# fullCURRENT_smarts_micro.net
KiCad netlist of a schematic drawn in Altium Designer
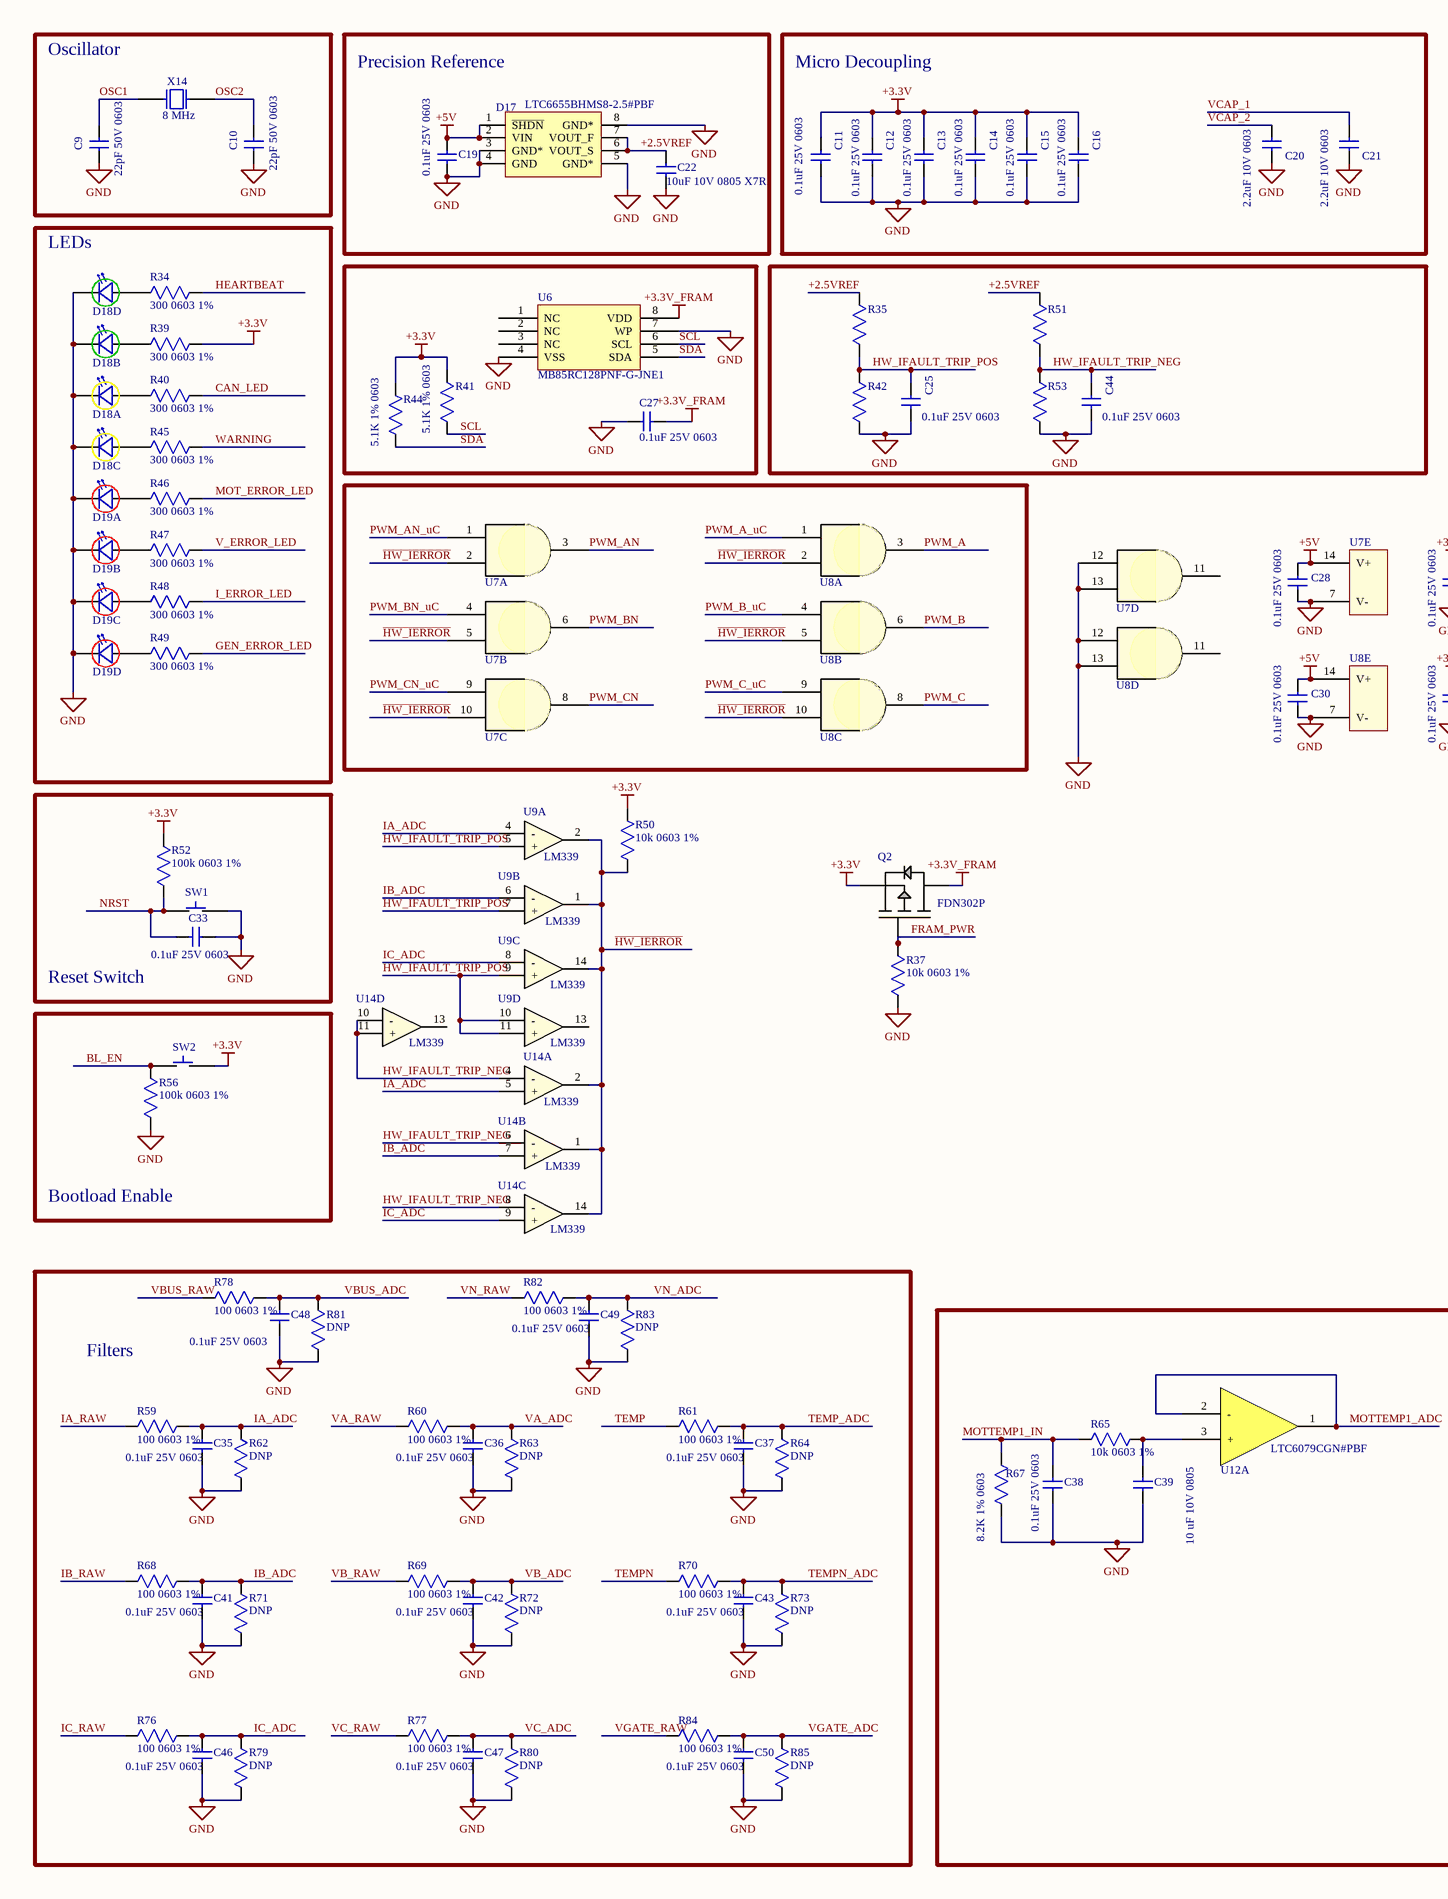
[diagram p0: fullCURRENT smarts micro.SchDoc, left]
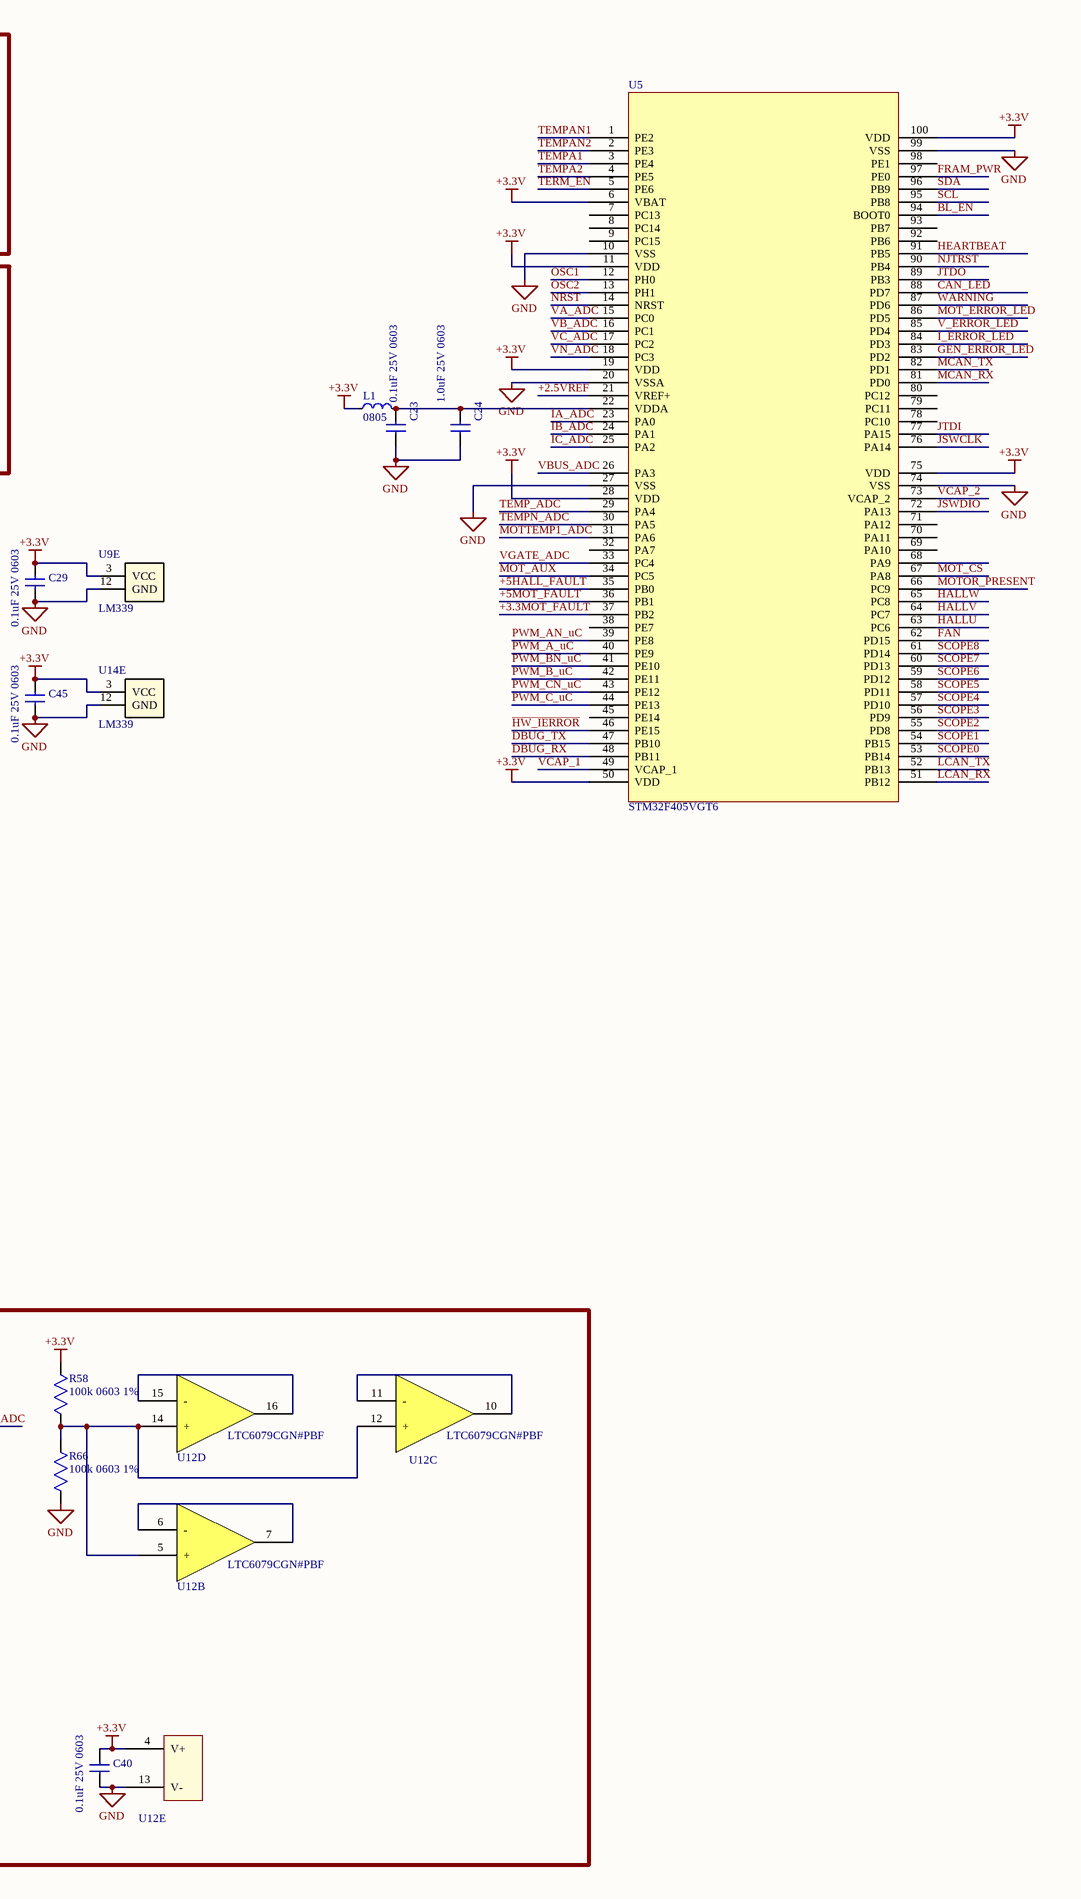
[diagram p1: fullCURRENT smarts micro.SchDoc, right]

(export (version "E")
  (design (tool "Eeschema 10.0.6"))
  (components
    (comp (ref "C9")
      (value "22pF 50V 0603")
      (footprint "0603_cap")
      (description "CAP CER 22PF 50V 5% NPO 0603")
      (fields (field (name "Comment") "CAP 0603"))
      (libsource (lib "Nutz") (part "C_0603"))
    )
    (comp (ref "C10")
      (value "22pF 50V 0603")
      (footprint "0603_cap")
      (description "CAP CER 22PF 50V 5% NPO 0603")
      (fields (field (name "Comment") "CAP 0603"))
      (libsource (lib "Nutz") (part "C_0603"))
    )
    (comp (ref "C11")
      (value "0.1uF 25V 0603")
      (footprint "0603_cap")
      (description "CAP CER 0.1UF 25V X7R 0603")
      (fields (field (name "PART NUMBER") "GRM188R71E104KA01D") (field (name "Comment") "CAP 0603"))
      (libsource (lib "Nutz") (part "C_0603"))
    )
    (comp (ref "C12")
      (value "0.1uF 25V 0603")
      (footprint "0603_cap")
      (description "CAP CER 0.1UF 25V X7R 0603")
      (fields (field (name "PART NUMBER") "GRM188R71E104KA01D") (field (name "Comment") "CAP 0603"))
      (libsource (lib "Nutz") (part "C_0603"))
    )
    (comp (ref "C13")
      (value "0.1uF 25V 0603")
      (footprint "0603_cap")
      (description "CAP CER 0.1UF 25V X7R 0603")
      (fields (field (name "PART NUMBER") "GRM188R71E104KA01D") (field (name "Comment") "CAP 0603"))
      (libsource (lib "Nutz") (part "C_0603"))
    )
    (comp (ref "C14")
      (value "0.1uF 25V 0603")
      (footprint "0603_cap")
      (description "CAP CER 0.1UF 25V X7R 0603")
      (fields (field (name "PART NUMBER") "GRM188R71E104KA01D") (field (name "Comment") "CAP 0603"))
      (libsource (lib "Nutz") (part "C_0603"))
    )
    (comp (ref "C15")
      (value "0.1uF 25V 0603")
      (footprint "0603_cap")
      (description "CAP CER 0.1UF 25V X7R 0603")
      (fields (field (name "PART NUMBER") "GRM188R71E104KA01D") (field (name "Comment") "CAP 0603"))
      (libsource (lib "Nutz") (part "C_0603"))
    )
    (comp (ref "C16")
      (value "0.1uF 25V 0603")
      (footprint "0603_cap")
      (description "CAP CER 0.1UF 25V X7R 0603")
      (fields (field (name "PART NUMBER") "GRM188R71E104KA01D") (field (name "Comment") "CAP 0603"))
      (libsource (lib "Nutz") (part "C_0603"))
    )
    (comp (ref "C19")
      (value "0.1uF 25V 0603")
      (footprint "0603_cap")
      (description "CAP CER 0.1UF 25V X7R 0603")
      (fields (field (name "Comment") "CAP 0603"))
      (libsource (lib "Nutz") (part "C_0603"))
    )
    (comp (ref "C20")
      (value "2.2uF 10V 0603")
      (footprint "0603_cap")
      (description "CAP CER 2.2UF 10V 10% X7R 0603")
      (fields (field (name "MANUFACTURER") "Taiyo Yuden") (field (name "PART NUMBER") "LMK107B7225KA-T"))
      (libsource (lib "Nutz") (part "C_0603"))
    )
    (comp (ref "C21")
      (value "2.2uF 10V 0603")
      (footprint "0603_cap")
      (description "CAP CER 2.2UF 10V 10% X7R 0603")
      (fields (field (name "MANUFACTURER") "Taiyo Yuden") (field (name "PART NUMBER") "LMK107B7225KA-T"))
      (libsource (lib "Nutz") (part "C_0603"))
    )
    (comp (ref "C22")
      (value "10uF 10V 0805 X7R")
      (footprint "0805_Capacitor")
      (description "CAP CERM 0805")
      (fields (field (name "Comment") "CAP 0805"))
      (libsource (lib "Nutz") (part "C_0805"))
    )
    (comp (ref "C23")
      (value "0.1uF 25V 0603")
      (footprint "0603_cap")
      (description "CAP CER 0.1UF 25V X7R 0603")
      (fields (field (name "PART NUMBER") "GRM188R71E104KA01D") (field (name "Comment") "CAP 0603"))
      (libsource (lib "Nutz") (part "C_0603"))
    )
    (comp (ref "C24")
      (value "1.0uF 25V 0603")
      (footprint "0603_cap")
      (description "CAP CER 1.0UF 25V 10% X7R 0603")
      (fields (field (name "Comment") "CAP 0603"))
      (libsource (lib "Nutz") (part "C_0603"))
    )
    (comp (ref "C25")
      (value "0.1uF 25V 0603")
      (footprint "0603_cap")
      (description "CAP CER 0.1UF 25V X7R 0603")
      (fields (field (name "PART NUMBER") "GRM188R71E104KA01D") (field (name "Comment") "CAP 0603"))
      (libsource (lib "Nutz") (part "C_0603"))
    )
    (comp (ref "C27")
      (value "0.1uF 25V 0603")
      (footprint "0603_cap")
      (description "CAP CER 0.1UF 25V X7R 0603")
      (fields (field (name "Comment") "CAP 0603"))
      (libsource (lib "Nutz") (part "C_0603"))
    )
    (comp (ref "C28")
      (value "0.1uF 25V 0603")
      (footprint "0603_cap")
      (description "CAP CER 0.1UF 25V X7R 0603")
      (fields (field (name "PART NUMBER") "GRM188R71E104KA01D") (field (name "Comment") "CAP 0603"))
      (libsource (lib "Nutz") (part "C_0603"))
    )
    (comp (ref "C29")
      (value "0.1uF 25V 0603")
      (footprint "0603_cap")
      (description "CAP CER 0.1UF 25V X7R 0603")
      (fields (field (name "PART NUMBER") "GRM188R71E104KA01D") (field (name "Comment") "CAP 0603"))
      (libsource (lib "Nutz") (part "C_0603"))
    )
    (comp (ref "C30")
      (value "0.1uF 25V 0603")
      (footprint "0603_cap")
      (description "CAP CER 0.1UF 25V X7R 0603")
      (fields (field (name "PART NUMBER") "GRM188R71E104KA01D") (field (name "Comment") "CAP 0603"))
      (libsource (lib "Nutz") (part "C_0603"))
    )
    (comp (ref "C33")
      (value "0.1uF 25V 0603")
      (footprint "0603_cap")
      (description "CAP CER 0.1UF 25V X7R 0603")
      (fields (field (name "PART NUMBER") "GRM188R71E104KA01D") (field (name "Comment") "CAP 0603"))
      (libsource (lib "Nutz") (part "C_0603"))
    )
    (comp (ref "C35")
      (value "0.1uF 25V 0603")
      (footprint "0603_cap")
      (description "CAP CER 0.1UF 25V X7R 0603")
      (fields (field (name "Comment") "CAP 0603"))
      (libsource (lib "Nutz") (part "C_0603"))
    )
    (comp (ref "C36")
      (value "0.1uF 25V 0603")
      (footprint "0603_cap")
      (description "CAP CER 0.1UF 25V X7R 0603")
      (fields (field (name "Comment") "CAP 0603"))
      (libsource (lib "Nutz") (part "C_0603"))
    )
    (comp (ref "C37")
      (value "0.1uF 25V 0603")
      (footprint "0603_cap")
      (description "CAP CER 0.1UF 25V X7R 0603")
      (fields (field (name "Comment") "CAP 0603"))
      (libsource (lib "Nutz") (part "C_0603"))
    )
    (comp (ref "C38")
      (value "0.1uF 25V 0603")
      (footprint "0603_cap")
      (description "CAP CER 0.1UF 25V X7R 0603")
      (fields (field (name "Comment") "CAP 0603"))
      (libsource (lib "Nutz") (part "C_0603"))
    )
    (comp (ref "C39")
      (value "10 uF 10V 0805")
      (footprint "0805_Capacitor")
      (description "CAP CER 10UF 10V 10% X5R 0805")
      (fields (field (name "MANUFACTURER") "Taiyo Yuden") (field (name "Comment") "CAP 0805"))
      (libsource (lib "Nutz") (part "C_0805"))
    )
    (comp (ref "C40")
      (value "0.1uF 25V 0603")
      (footprint "0603_cap")
      (description "CAP CER 0.1UF 25V X7R 0603")
      (fields (field (name "PART NUMBER") "GRM188R71E104KA01D") (field (name "Comment") "CAP 0603"))
      (libsource (lib "Nutz") (part "C_0603"))
    )
    (comp (ref "C41")
      (value "0.1uF 25V 0603")
      (footprint "0603_cap")
      (description "CAP CER 0.1UF 25V X7R 0603")
      (fields (field (name "Comment") "CAP 0603"))
      (libsource (lib "Nutz") (part "C_0603"))
    )
    (comp (ref "C42")
      (value "0.1uF 25V 0603")
      (footprint "0603_cap")
      (description "CAP CER 0.1UF 25V X7R 0603")
      (fields (field (name "Comment") "CAP 0603"))
      (libsource (lib "Nutz") (part "C_0603"))
    )
    (comp (ref "C43")
      (value "0.1uF 25V 0603")
      (footprint "0603_cap")
      (description "CAP CER 0.1UF 25V X7R 0603")
      (fields (field (name "Comment") "CAP 0603"))
      (libsource (lib "Nutz") (part "C_0603"))
    )
    (comp (ref "C44")
      (value "0.1uF 25V 0603")
      (footprint "0603_cap")
      (description "CAP CER 0.1UF 25V X7R 0603")
      (fields (field (name "PART NUMBER") "GRM188R71E104KA01D") (field (name "Comment") "CAP 0603"))
      (libsource (lib "Nutz") (part "C_0603"))
    )
    (comp (ref "C45")
      (value "0.1uF 25V 0603")
      (footprint "0603_cap")
      (description "CAP CER 0.1UF 25V X7R 0603")
      (fields (field (name "PART NUMBER") "GRM188R71E104KA01D") (field (name "Comment") "CAP 0603"))
      (libsource (lib "Nutz") (part "C_0603"))
    )
    (comp (ref "C46")
      (value "0.1uF 25V 0603")
      (footprint "0603_cap")
      (description "CAP CER 0.1UF 25V X7R 0603")
      (fields (field (name "Comment") "CAP 0603"))
      (libsource (lib "Nutz") (part "C_0603"))
    )
    (comp (ref "C47")
      (value "0.1uF 25V 0603")
      (footprint "0603_cap")
      (description "CAP CER 0.1UF 25V X7R 0603")
      (fields (field (name "Comment") "CAP 0603"))
      (libsource (lib "Nutz") (part "C_0603"))
    )
    (comp (ref "C48")
      (value "0.1uF 25V 0603")
      (footprint "0603_cap")
      (description "CAP CER 0.1UF 25V X7R 0603")
      (fields (field (name "Comment") "CAP 0603"))
      (libsource (lib "Nutz") (part "C_0603"))
    )
    (comp (ref "C49")
      (value "0.1uF 25V 0603")
      (footprint "0603_cap")
      (description "CAP CER 0.1UF 25V X7R 0603")
      (fields (field (name "Comment") "CAP 0603"))
      (libsource (lib "Nutz") (part "C_0603"))
    )
    (comp (ref "C50")
      (value "0.1uF 25V 0603")
      (footprint "0603_cap")
      (description "CAP CER 0.1UF 25V X7R 0603")
      (fields (field (name "Comment") "CAP 0603"))
      (libsource (lib "Nutz") (part "C_0603"))
    )
    (comp (ref "D17")
      (value "D_LTC6655BHMS8-2.5#PBF")
      (footprint "TSOP65P490X110-8N")
      (description "IC VREF SERIES PREC 2.5V 8-MSOP")
      (fields
        (field (name "MANUFACTURER") "Linear Technology")
        (field (name "PART NUMBER") "LTC6655BHMS8-2.5#PBF")
      )
      (libsource (lib "c3_SchLib") (part "D_LTC6655BHMS8-3.3#PBF"))
    )
    (comp (ref "D18")
      (value "D_LED_4HIGH_2GREEN_2YELLOW")
      (footprint "DIALIGHT 568")
      (description "LED 4HI 3MM GRN/YEL/GRN/YEL PCMT")
      (fields (field (name "PART NUMBER") "568-0102-323F") (field (name "MANUFACTURER") "Dialight"))
      (libsource (lib "Nutz") (part "D_LED_4HIGH_2GREEN_2YELLOW"))
    )
    (comp (ref "D19")
      (value "D_LED_4HIGH_RED")
      (footprint "DIALIGHT 568")
      (description "LED 4HI 3MM 5V RED PC MNT")
      (fields (field (name "PART NUMBER") "568-0301-111F") (field (name "MANUFACTURER") "Dialight"))
      (libsource (lib "Nutz") (part "D_LED_4HIGH_RED"))
    )
    (comp (ref "L1")
      (value "0805")
      (footprint "0805_Resistor")
      (description "FERRITE 0603")
      (libsource (lib "d1_SchLib") (part "L_1mH_10%"))
    )
    (comp (ref "Q2")
      (value "FDN302P")
      (footprint "SOT-23")
      (description "MOSFET P-CH 20V 2.4A SSOT3")
      (fields
        (field (name "MANUFACTURER") "Fairchild Semiconductor")
        (field (name "SVP CREATOR") "Adam Shea")
        (field (name "SVP REVIEWER 1") "Nate Bolyard")
        (field (name "SVP REVIEWER 2") "Trevtron")
      )
      (libsource (lib "d1_SchLib") (part "Q_FDN302P"))
    )
    (comp (ref "R34")
      (value "300 0603 1%")
      (footprint "0603_res")
      (description "RES 300 0603 1%")
      (fields (field (name "Comment") "RES 0603"))
      (libsource (lib "Nutz") (part "R_0603"))
    )
    (comp (ref "R35")
      (value "RES 0603")
      (footprint "0603_res")
      (description "RES DNP 0603 0.1%")
      (libsource (lib "Nutz") (part "R_0603"))
    )
    (comp (ref "R37")
      (value "10k 0603 1%")
      (footprint "0603_res")
      (description "RES 10K 0603 1%")
      (fields (field (name "Comment") "RES 0603"))
      (libsource (lib "Nutz") (part "R_0603"))
    )
    (comp (ref "R39")
      (value "300 0603 1%")
      (footprint "0603_res")
      (description "RES 300 0603 1%")
      (fields (field (name "Comment") "RES 0603"))
      (libsource (lib "Nutz") (part "R_0603"))
    )
    (comp (ref "R40")
      (value "300 0603 1%")
      (footprint "0603_res")
      (description "RES 300 0603 1%")
      (fields (field (name "Comment") "RES 0603"))
      (libsource (lib "Nutz") (part "R_0603"))
    )
    (comp (ref "R41")
      (value "5.1K 1% 0603")
      (footprint "0603_res")
      (description "RES 5.1K 1% 0603")
      (fields (field (name "Comment") "RES 0603"))
      (libsource (lib "Nutz") (part "R_0603"))
    )
    (comp (ref "R42")
      (value "RES 0603")
      (footprint "0603_res")
      (description "RES DNP 0603 0.1%")
      (libsource (lib "Nutz") (part "R_0603"))
    )
    (comp (ref "R44")
      (value "5.1K 1% 0603")
      (footprint "0603_res")
      (description "RES 5.1K 1% 0603")
      (fields (field (name "Comment") "RES 0603"))
      (libsource (lib "Nutz") (part "R_0603"))
    )
    (comp (ref "R45")
      (value "300 0603 1%")
      (footprint "0603_res")
      (description "RES 300 0603 1%")
      (fields (field (name "Comment") "RES 0603"))
      (libsource (lib "Nutz") (part "R_0603"))
    )
    (comp (ref "R46")
      (value "300 0603 1%")
      (footprint "0603_res")
      (description "RES 300 0603 1%")
      (fields (field (name "Comment") "RES 0603"))
      (libsource (lib "Nutz") (part "R_0603"))
    )
    (comp (ref "R47")
      (value "300 0603 1%")
      (footprint "0603_res")
      (description "RES 300 0603 1%")
      (fields (field (name "Comment") "RES 0603"))
      (libsource (lib "Nutz") (part "R_0603"))
    )
    (comp (ref "R48")
      (value "300 0603 1%")
      (footprint "0603_res")
      (description "RES 300 0603 1%")
      (fields (field (name "Comment") "RES 0603"))
      (libsource (lib "Nutz") (part "R_0603"))
    )
    (comp (ref "R49")
      (value "300 0603 1%")
      (footprint "0603_res")
      (description "RES 300 0603 1%")
      (fields (field (name "Comment") "RES 0603"))
      (libsource (lib "Nutz") (part "R_0603"))
    )
    (comp (ref "R50")
      (value "10k 0603 1%")
      (footprint "0603_res")
      (description "RES 10K 0603 1%")
      (fields (field (name "Comment") "RES 0603"))
      (libsource (lib "Nutz") (part "R_0603"))
    )
    (comp (ref "R51")
      (value "RES 0603")
      (footprint "0603_res")
      (description "RES DNP 0603 0.1%")
      (libsource (lib "Nutz") (part "R_0603"))
    )
    (comp (ref "R52")
      (value "100k 0603 1%")
      (footprint "0603_res")
      (description "RES 100K 0603 1%")
      (fields (field (name "Comment") "RES 0603"))
      (libsource (lib "Nutz") (part "R_0603"))
    )
    (comp (ref "R53")
      (value "RES 0603")
      (footprint "0603_res")
      (description "RES DNP 0603 0.1%")
      (libsource (lib "Nutz") (part "R_0603"))
    )
    (comp (ref "R56")
      (value "100k 0603 1%")
      (footprint "0603_res")
      (description "RES 100K 0603 1%")
      (fields (field (name "Comment") "RES 0603"))
      (libsource (lib "Nutz") (part "R_0603"))
    )
    (comp (ref "R58")
      (value "100k 0603 1%")
      (footprint "0603_res")
      (description "RES 100K 0603 1%")
      (fields (field (name "Comment") "RES 0603"))
      (libsource (lib "Nutz") (part "R_0603"))
    )
    (comp (ref "R59")
      (value "100 0603 1%")
      (footprint "0603_res")
      (description "RES 100 0603 1%")
      (fields (field (name "Comment") "RES 0603"))
      (libsource (lib "Nutz") (part "R_0603"))
    )
    (comp (ref "R60")
      (value "100 0603 1%")
      (footprint "0603_res")
      (description "RES 100 0603 1%")
      (fields (field (name "Comment") "RES 0603"))
      (libsource (lib "Nutz") (part "R_0603"))
    )
    (comp (ref "R61")
      (value "100 0603 1%")
      (footprint "0603_res")
      (description "RES 100 0603 1%")
      (fields (field (name "Comment") "RES 0603"))
      (libsource (lib "Nutz") (part "R_0603"))
    )
    (comp (ref "R62")
      (value "DNP")
      (footprint "0603_res")
      (description "RES 0603 DNP")
      (fields (field (name "Comment") "RES 0603"))
      (libsource (lib "Nutz") (part "R_0603"))
    )
    (comp (ref "R63")
      (value "DNP")
      (footprint "0603_res")
      (description "RES 0603 DNP")
      (fields (field (name "Comment") "RES 0603"))
      (libsource (lib "Nutz") (part "R_0603"))
    )
    (comp (ref "R64")
      (value "DNP")
      (footprint "0603_res")
      (description "RES 0603 DNP")
      (fields (field (name "Comment") "RES 0603"))
      (libsource (lib "Nutz") (part "R_0603"))
    )
    (comp (ref "R65")
      (value "10k 0603 1%")
      (footprint "0603_res")
      (description "RES 10K 0603 1%")
      (fields (field (name "Comment") "RES 0603"))
      (libsource (lib "Nutz") (part "R_0603"))
    )
    (comp (ref "R66")
      (value "100k 0603 1%")
      (footprint "0603_res")
      (description "RES 100K 0603 1%")
      (fields (field (name "Comment") "RES 0603"))
      (libsource (lib "Nutz") (part "R_0603"))
    )
    (comp (ref "R67")
      (value "8.2K 1% 0603")
      (footprint "0603_res")
      (description "RES 8.2K 1% 0603")
      (fields (field (name "Comment") "RES 0603"))
      (libsource (lib "Nutz") (part "R_0603"))
    )
    (comp (ref "R68")
      (value "100 0603 1%")
      (footprint "0603_res")
      (description "RES 100 0603 1%")
      (fields (field (name "Comment") "RES 0603"))
      (libsource (lib "Nutz") (part "R_0603"))
    )
    (comp (ref "R69")
      (value "100 0603 1%")
      (footprint "0603_res")
      (description "RES 100 0603 1%")
      (fields (field (name "Comment") "RES 0603"))
      (libsource (lib "Nutz") (part "R_0603"))
    )
    (comp (ref "R70")
      (value "100 0603 1%")
      (footprint "0603_res")
      (description "RES 100 0603 1%")
      (fields (field (name "Comment") "RES 0603"))
      (libsource (lib "Nutz") (part "R_0603"))
    )
    (comp (ref "R71")
      (value "DNP")
      (footprint "0603_res")
      (description "RES 0603 DNP")
      (fields (field (name "Comment") "RES 0603"))
      (libsource (lib "Nutz") (part "R_0603"))
    )
    (comp (ref "R72")
      (value "DNP")
      (footprint "0603_res")
      (description "RES 0603 DNP")
      (fields (field (name "Comment") "RES 0603"))
      (libsource (lib "Nutz") (part "R_0603"))
    )
    (comp (ref "R73")
      (value "DNP")
      (footprint "0603_res")
      (description "RES 0603 DNP")
      (fields (field (name "Comment") "RES 0603"))
      (libsource (lib "Nutz") (part "R_0603"))
    )
    (comp (ref "R76")
      (value "100 0603 1%")
      (footprint "0603_res")
      (description "RES 100 0603 1%")
      (fields (field (name "Comment") "RES 0603"))
      (libsource (lib "Nutz") (part "R_0603"))
    )
    (comp (ref "R77")
      (value "100 0603 1%")
      (footprint "0603_res")
      (description "RES 100 0603 1%")
      (fields (field (name "Comment") "RES 0603"))
      (libsource (lib "Nutz") (part "R_0603"))
    )
    (comp (ref "R78")
      (value "100 0603 1%")
      (footprint "0603_res")
      (description "RES 100 0603 1%")
      (fields (field (name "Comment") "RES 0603"))
      (libsource (lib "Nutz") (part "R_0603"))
    )
    (comp (ref "R79")
      (value "DNP")
      (footprint "0603_res")
      (description "RES 0603 DNP")
      (fields (field (name "Comment") "RES 0603"))
      (libsource (lib "Nutz") (part "R_0603"))
    )
    (comp (ref "R80")
      (value "DNP")
      (footprint "0603_res")
      (description "RES 0603 DNP")
      (fields (field (name "Comment") "RES 0603"))
      (libsource (lib "Nutz") (part "R_0603"))
    )
    (comp (ref "R81")
      (value "DNP")
      (footprint "0603_res")
      (description "RES 0603 DNP")
      (fields (field (name "Comment") "RES 0603"))
      (libsource (lib "Nutz") (part "R_0603"))
    )
    (comp (ref "R82")
      (value "100 0603 1%")
      (footprint "0603_res")
      (description "RES 100 0603 1%")
      (fields (field (name "Comment") "RES 0603"))
      (libsource (lib "Nutz") (part "R_0603"))
    )
    (comp (ref "R83")
      (value "DNP")
      (footprint "0603_res")
      (description "RES 0603 DNP")
      (fields (field (name "Comment") "RES 0603"))
      (libsource (lib "Nutz") (part "R_0603"))
    )
    (comp (ref "R84")
      (value "100 0603 1%")
      (footprint "0603_res")
      (description "RES 100 0603 1%")
      (fields (field (name "Comment") "RES 0603"))
      (libsource (lib "Nutz") (part "R_0603"))
    )
    (comp (ref "R85")
      (value "DNP")
      (footprint "0603_res")
      (description "RES 0603 DNP")
      (fields (field (name "Comment") "RES 0603"))
      (libsource (lib "Nutz") (part "R_0603"))
    )
    (comp (ref "SW1")
      (value "SW_TACT_SWITCH_6x6")
      (footprint "TACT_SWITCH_6x6")
      (description "SWITCH TACTILE SPST-NO 0.05A 12V")
      (fields (field (name "MANUFACTURER") "C&K Components") (field (name "PART NUMBER") "PTS645SK43 LFS"))
      (libsource (lib "d1_SchLib") (part "SW_TACT_SWITCH_6x6"))
    )
    (comp (ref "SW2")
      (value "SW_TACT_SWITCH_6x6")
      (footprint "TACT_SWITCH_6x6")
      (description "SWITCH TACTILE SPST-NO 0.05A 12V")
      (fields (field (name "MANUFACTURER") "C&K Components") (field (name "PART NUMBER") "PTS645SK43 LFS"))
      (libsource (lib "d1_SchLib") (part "SW_TACT_SWITCH_6x6"))
    )
    (comp (ref "U5")
      (value "STM32F405VGT6")
      (footprint "STM32F405VG")
      (description "IC MCU 32BIT 1MB FLASH 100LQFP")
      (fields (field (name "MANUFACTURER") "STMicroelectronics"))
      (libsource (lib "Nutz") (part "U_STM32F405VGT6"))
    )
    (comp (ref "U6")
      (value "MB85RC128PNF-G-JNE1")
      (footprint "SOIC127P600X175-8N")
      (description "IC FRAM 128KBIT 400KHZ 8SOP")
      (fields
        (field (name "MANUFACTURER") "Fujitsu Semiconductor America Inc")
        (field (name "PART NUMBER") "MB85RC128PNF-G-JNE1")
      )
      (libsource (lib "c3_SchLib") (part "U_MB85RC16PNF-G-JNE1"))
    )
    (comp (ref "U7")
      (value "74LVC08AT14-13")
      (footprint "TSSOP-14-DIODES")
      (description "IC QUAD 2-IN AND GATE 14TSSOP")
      (fields (field (name "MANUFACTURER") "Diodes, Inc."))
      (libsource (lib "Nutz") (part "U_74LVC08AT14-13"))
    )
    (comp (ref "U8")
      (value "74LVC08AT14-13")
      (footprint "TSSOP-14-DIODES")
      (description "IC QUAD 2-IN AND GATE 14TSSOP")
      (fields (field (name "MANUFACTURER") "Diodes, Inc."))
      (libsource (lib "Nutz") (part "U_74LVC08AT14-13"))
    )
    (comp (ref "U9") (value "LM339") (footprint "SOIC127P600X175-14N") (libsource (lib "dps") (part "LM339")))
    (comp (ref "U12")
      (value "U_LTC6079CGN")
      (footprint "SSOP-16")
      (description "IC OP AMP QUAD R-R I/O 16SSOP")
      (fields (field (name "MANUFACTURER") "LT") (field (name "PART NUMBER") "LTC6079CGN#PBF"))
      (libsource (lib "Nutz") (part "U_LTC6079CGN"))
    )
    (comp (ref "U14")
      (value "LM339")
      (footprint "SOIC127P600X175-14N")
      (libsource (lib "dps") (part "LM339"))
    )
    (comp (ref "X14")
      (value "8 MHz")
      (footprint "HC-49")
      (description "CRYSTAL 8.0 MHZ 20PF")
      (fields (field (name "PART NUMBER") "FOXSLF/080-20") (field (name "MANUFACTURER") "Fox Electronics"))
      (libsource (lib "d1_SchLib") (part "X_HC49"))
    )
  )
  (nets
    (net (code "1") (name "+3.3V") (class "Default")
      (node (ref "C11") (pin "2") (pinfunction "2_2") (pintype "passive"))
      (node (ref "C12") (pin "2") (pinfunction "2_2") (pintype "passive"))
      (node (ref "C13") (pin "2") (pinfunction "2_2") (pintype "passive"))
      (node (ref "C14") (pin "2") (pinfunction "2_2") (pintype "passive"))
      (node (ref "C15") (pin "2") (pinfunction "2_2") (pintype "passive"))
      (node (ref "C16") (pin "2") (pinfunction "2_2") (pintype "passive"))
      (node (ref "C29") (pin "2") (pinfunction "2_2") (pintype "passive"))
      (node (ref "C40") (pin "2") (pinfunction "2_2") (pintype "passive"))
      (node (ref "C45") (pin "2") (pinfunction "2_2") (pintype "passive"))
      (node (ref "L1") (pin "1") (pinfunction "1_1") (pintype "passive"))
      (node (ref "Q2") (pin "2") (pinfunction "SOURCE_2") (pintype "passive"))
      (node (ref "R39") (pin "1") (pinfunction "1_1") (pintype "passive"))
      (node (ref "R41") (pin "1") (pinfunction "1_1") (pintype "passive"))
      (node (ref "R44") (pin "1") (pinfunction "1_1") (pintype "passive"))
      (node (ref "R50") (pin "1") (pinfunction "1_1") (pintype "passive"))
      (node (ref "R52") (pin "1") (pinfunction "1_1") (pintype "passive"))
      (node (ref "R58") (pin "1") (pinfunction "1_1") (pintype "passive"))
      (node (ref "SW2") (pin "2") (pinfunction "2_2") (pintype "passive"))
      (node (ref "U12") (pin "4") (pinfunction "V+_4") (pintype "passive"))
      (node (ref "U14") (pin "3") (pinfunction "VCC_3") (pintype "passive"))
      (node (ref "U5") (pin "100") (pinfunction "VDD_100") (pintype "passive"))
      (node (ref "U5") (pin "11") (pinfunction "VDD_11") (pintype "passive"))
      (node (ref "U5") (pin "19") (pinfunction "VDD_19") (pintype "passive"))
      (node (ref "U5") (pin "28") (pinfunction "VDD_28") (pintype "passive"))
      (node (ref "U5") (pin "50") (pinfunction "VDD_50") (pintype "passive"))
      (node (ref "U5") (pin "6") (pinfunction "VBAT_6") (pintype "passive"))
      (node (ref "U5") (pin "75") (pinfunction "VDD_75") (pintype "passive"))
      (node (ref "U9") (pin "3") (pinfunction "VCC_3") (pintype "passive"))
    )
    (net (code "2") (name "+3.3V_FRAM") (class "Default")
      (node (ref "C27") (pin "1") (pinfunction "1_1") (pintype "passive"))
      (node (ref "Q2") (pin "3") (pinfunction "DRAIN_3") (pintype "passive"))
      (node (ref "U6") (pin "8") (pinfunction "VDD_8") (pintype "passive"))
    )
    (net (code "3") (name "+5V") (class "Default")
      (node (ref "C19") (pin "1") (pinfunction "1_1") (pintype "passive"))
      (node (ref "C28") (pin "2") (pinfunction "2_2") (pintype "passive"))
      (node (ref "C30") (pin "2") (pinfunction "2_2") (pintype "passive"))
      (node (ref "D17") (pin "1") (pinfunction "~{SHDN}_1") (pintype "passive"))
      (node (ref "D17") (pin "2") (pinfunction "VIN_2") (pintype "passive"))
      (node (ref "U7") (pin "14") (pinfunction "V+_14") (pintype "passive"))
      (node (ref "U8") (pin "14") (pinfunction "V+_14") (pintype "passive"))
    )
    (net (code "4") (name "/+2.5VREF") (class "Default")
      (node (ref "C22") (pin "1") (pinfunction "1_1") (pintype "passive"))
      (node (ref "D17") (pin "6") (pinfunction "VOUT_S_6") (pintype "passive"))
      (node (ref "D17") (pin "7") (pinfunction "VOUT_F_7") (pintype "passive"))
      (node (ref "R35") (pin "1") (pinfunction "1_1") (pintype "passive"))
      (node (ref "R51") (pin "1") (pinfunction "1_1") (pintype "passive"))
      (node (ref "U5") (pin "21") (pinfunction "VREF+_21") (pintype "passive"))
    )
    (net (code "5") (name "/+3.3MOT_FAULT") (class "Default")
      (node (ref "U5") (pin "37") (pinfunction "PB2_37") (pintype "passive"))
    )
    (net (code "6") (name "/+5HALL_FAULT") (class "Default")
      (node (ref "U5") (pin "35") (pinfunction "PB0_35") (pintype "passive"))
    )
    (net (code "7") (name "/+5MOT_FAULT") (class "Default")
      (node (ref "U5") (pin "36") (pinfunction "PB1_36") (pintype "passive"))
    )
    (net (code "8") (name "/BL_EN") (class "Default")
      (node (ref "R56") (pin "1") (pinfunction "1_1") (pintype "passive"))
      (node (ref "SW2") (pin "1") (pinfunction "1_1") (pintype "passive"))
      (node (ref "U5") (pin "94") (pinfunction "BOOT0_94") (pintype "passive"))
    )
    (net (code "9") (name "/CAN_LED") (class "Default")
      (node (ref "R40") (pin "1") (pinfunction "1_1") (pintype "passive"))
      (node (ref "U5") (pin "88") (pinfunction "PD7_88") (pintype "passive"))
    )
    (net (code "10") (name "/DBUG_RX") (class "Default")
      (node (ref "U5") (pin "48") (pinfunction "PB11_48") (pintype "passive"))
    )
    (net (code "11") (name "/DBUG_TX") (class "Default")
      (node (ref "U5") (pin "47") (pinfunction "PB10_47") (pintype "passive"))
    )
    (net (code "12") (name "/FAN") (class "Default")
      (node (ref "U5") (pin "62") (pinfunction "PD15_62") (pintype "passive"))
    )
    (net (code "13") (name "/FRAM_PWR") (class "Default")
      (node (ref "Q2") (pin "1") (pinfunction "GATE_1") (pintype "passive"))
      (node (ref "R37") (pin "1") (pinfunction "1_1") (pintype "passive"))
      (node (ref "U5") (pin "97") (pinfunction "PE0_97") (pintype "passive"))
    )
    (net (code "14") (name "/GEN_ERROR_LED") (class "Default")
      (node (ref "R49") (pin "1") (pinfunction "1_1") (pintype "passive"))
      (node (ref "U5") (pin "83") (pinfunction "PD2_83") (pintype "passive"))
    )
    (net (code "15") (name "/HALLU") (class "Default")
      (node (ref "U5") (pin "63") (pinfunction "PC6_63") (pintype "passive"))
    )
    (net (code "16") (name "/HALLV") (class "Default")
      (node (ref "U5") (pin "64") (pinfunction "PC7_64") (pintype "passive"))
    )
    (net (code "17") (name "/HALLW") (class "Default")
      (node (ref "U5") (pin "65") (pinfunction "PC8_65") (pintype "passive"))
    )
    (net (code "18") (name "/HEARTBEAT") (class "Default")
      (node (ref "R34") (pin "1") (pinfunction "1_1") (pintype "passive"))
      (node (ref "U5") (pin "91") (pinfunction "PB5_91") (pintype "passive"))
    )
    (net (code "19") (name "/HW_IFAULT_TRIP_NEG") (class "Default")
      (node (ref "C44") (pin "2") (pinfunction "2_2") (pintype "passive"))
      (node (ref "R51") (pin "2") (pinfunction "2_2") (pintype "passive"))
      (node (ref "R53") (pin "1") (pinfunction "1_1") (pintype "passive"))
      (node (ref "U14") (pin "10") (pinfunction "-_10") (pintype "passive"))
      (node (ref "U14") (pin "11") (pinfunction "+_11") (pintype "passive"))
      (node (ref "U14") (pin "4") (pinfunction "-_4") (pintype "passive"))
      (node (ref "U14") (pin "6") (pinfunction "-_6") (pintype "passive"))
      (node (ref "U14") (pin "8") (pinfunction "-_8") (pintype "passive"))
    )
    (net (code "20") (name "/HW_IFAULT_TRIP_POS") (class "Default")
      (node (ref "C25") (pin "2") (pinfunction "2_2") (pintype "passive"))
      (node (ref "R35") (pin "2") (pinfunction "2_2") (pintype "passive"))
      (node (ref "R42") (pin "1") (pinfunction "1_1") (pintype "passive"))
      (node (ref "U9") (pin "10") (pinfunction "-_10") (pintype "passive"))
      (node (ref "U9") (pin "11") (pinfunction "+_11") (pintype "passive"))
      (node (ref "U9") (pin "5") (pinfunction "+_5") (pintype "passive"))
      (node (ref "U9") (pin "7") (pinfunction "+_7") (pintype "passive"))
      (node (ref "U9") (pin "9") (pinfunction "+_9") (pintype "passive"))
    )
    (net (code "21") (name "/IA_ADC") (class "Default")
      (node (ref "C35") (pin "2") (pinfunction "2_2") (pintype "passive"))
      (node (ref "R59") (pin "1") (pinfunction "1_1") (pintype "passive"))
      (node (ref "R62") (pin "2") (pinfunction "2_2") (pintype "passive"))
      (node (ref "U14") (pin "5") (pinfunction "+_5") (pintype "passive"))
      (node (ref "U5") (pin "23") (pinfunction "PA0_23") (pintype "passive"))
      (node (ref "U9") (pin "4") (pinfunction "-_4") (pintype "passive"))
    )
    (net (code "22") (name "/IA_RAW") (class "Default")
      (node (ref "R59") (pin "2") (pinfunction "2_2") (pintype "passive"))
    )
    (net (code "23") (name "/IB_ADC") (class "Default")
      (node (ref "C41") (pin "2") (pinfunction "2_2") (pintype "passive"))
      (node (ref "R68") (pin "1") (pinfunction "1_1") (pintype "passive"))
      (node (ref "R71") (pin "2") (pinfunction "2_2") (pintype "passive"))
      (node (ref "U14") (pin "7") (pinfunction "+_7") (pintype "passive"))
      (node (ref "U5") (pin "24") (pinfunction "PA1_24") (pintype "passive"))
      (node (ref "U9") (pin "6") (pinfunction "-_6") (pintype "passive"))
    )
    (net (code "24") (name "/IB_RAW") (class "Default")
      (node (ref "R68") (pin "2") (pinfunction "2_2") (pintype "passive"))
    )
    (net (code "25") (name "/IC_ADC") (class "Default")
      (node (ref "C46") (pin "2") (pinfunction "2_2") (pintype "passive"))
      (node (ref "R76") (pin "1") (pinfunction "1_1") (pintype "passive"))
      (node (ref "R79") (pin "2") (pinfunction "2_2") (pintype "passive"))
      (node (ref "U14") (pin "9") (pinfunction "+_9") (pintype "passive"))
      (node (ref "U5") (pin "25") (pinfunction "PA2_25") (pintype "passive"))
      (node (ref "U9") (pin "8") (pinfunction "-_8") (pintype "passive"))
    )
    (net (code "26") (name "/IC_RAW") (class "Default")
      (node (ref "R76") (pin "2") (pinfunction "2_2") (pintype "passive"))
    )
    (net (code "27") (name "/I_ERROR_LED") (class "Default")
      (node (ref "R48") (pin "1") (pinfunction "1_1") (pintype "passive"))
      (node (ref "U5") (pin "84") (pinfunction "PD3_84") (pintype "passive"))
    )
    (net (code "28") (name "/JSWCLK") (class "Default")
      (node (ref "U5") (pin "76") (pinfunction "PA14_76") (pintype "passive"))
    )
    (net (code "29") (name "/JSWDIO") (class "Default")
      (node (ref "U5") (pin "72") (pinfunction "PA13_72") (pintype "passive"))
    )
    (net (code "30") (name "/JTDI") (class "Default")
      (node (ref "U5") (pin "77") (pinfunction "PA15_77") (pintype "passive"))
    )
    (net (code "31") (name "/JTDO") (class "Default")
      (node (ref "U5") (pin "89") (pinfunction "PB3_89") (pintype "passive"))
    )
    (net (code "32") (name "/LCAN_RX") (class "Default")
      (node (ref "U5") (pin "51") (pinfunction "PB12_51") (pintype "passive"))
    )
    (net (code "33") (name "/LCAN_TX") (class "Default")
      (node (ref "U5") (pin "52") (pinfunction "PB13_52") (pintype "passive"))
    )
    (net (code "34") (name "/MCAN_RX") (class "Default")
      (node (ref "U5") (pin "81") (pinfunction "PD0_81") (pintype "passive"))
    )
    (net (code "35") (name "/MCAN_TX") (class "Default")
      (node (ref "U5") (pin "82") (pinfunction "PD1_82") (pintype "passive"))
    )
    (net (code "36") (name "/MOTOR_PRESENT") (class "Default")
      (node (ref "U5") (pin "66") (pinfunction "PC9_66") (pintype "passive"))
    )
    (net (code "37") (name "/MOTTEMP1_ADC") (class "Default")
      (node (ref "U12") (pin "1") (pinfunction "1_1") (pintype "passive"))
      (node (ref "U12") (pin "2") (pinfunction "-_2") (pintype "passive"))
      (node (ref "U5") (pin "31") (pinfunction "PA6_31") (pintype "passive"))
    )
    (net (code "38") (name "/MOTTEMP1_IN") (class "Default")
      (node (ref "C38") (pin "1") (pinfunction "1_1") (pintype "passive"))
      (node (ref "R65") (pin "2") (pinfunction "2_2") (pintype "passive"))
      (node (ref "R67") (pin "1") (pinfunction "1_1") (pintype "passive"))
    )
    (net (code "39") (name "/MOT_AUX") (class "Default")
      (node (ref "U5") (pin "34") (pinfunction "PC5_34") (pintype "passive"))
    )
    (net (code "40") (name "/MOT_CS") (class "Default")
      (node (ref "U5") (pin "67") (pinfunction "PA8_67") (pintype "passive"))
    )
    (net (code "41") (name "/MOT_ERROR_LED") (class "Default")
      (node (ref "R46") (pin "1") (pinfunction "1_1") (pintype "passive"))
      (node (ref "U5") (pin "86") (pinfunction "PD5_86") (pintype "passive"))
    )
    (net (code "42") (name "/NJTRST") (class "Default")
      (node (ref "U5") (pin "90") (pinfunction "PB4_90") (pintype "passive"))
    )
    (net (code "43") (name "/NRST") (class "Default")
      (node (ref "C33") (pin "1") (pinfunction "1_1") (pintype "passive"))
      (node (ref "R52") (pin "2") (pinfunction "2_2") (pintype "passive"))
      (node (ref "SW1") (pin "1") (pinfunction "1_1") (pintype "passive"))
      (node (ref "U5") (pin "14") (pinfunction "NRST_14") (pintype "passive"))
    )
    (net (code "44") (name "/OSC1") (class "Default")
      (node (ref "C9") (pin "1") (pinfunction "1_1") (pintype "passive"))
      (node (ref "U5") (pin "12") (pinfunction "PH0_12") (pintype "passive"))
      (node (ref "X14") (pin "1") (pinfunction "1_1") (pintype "passive"))
    )
    (net (code "45") (name "/OSC2") (class "Default")
      (node (ref "C10") (pin "1") (pinfunction "1_1") (pintype "passive"))
      (node (ref "U5") (pin "13") (pinfunction "PH1_13") (pintype "passive"))
      (node (ref "X14") (pin "2") (pinfunction "2_2") (pintype "passive"))
    )
    (net (code "46") (name "/PWM_A") (class "Default")
      (node (ref "U8") (pin "3") (pinfunction "3_3") (pintype "passive"))
    )
    (net (code "47") (name "/PWM_AN") (class "Default")
      (node (ref "U7") (pin "3") (pinfunction "3_3") (pintype "passive"))
    )
    (net (code "48") (name "/PWM_AN_uC") (class "Default")
      (node (ref "U5") (pin "39") (pinfunction "PE8_39") (pintype "passive"))
      (node (ref "U7") (pin "1") (pinfunction "1_1") (pintype "passive"))
    )
    (net (code "49") (name "/PWM_A_uC") (class "Default")
      (node (ref "U5") (pin "40") (pinfunction "PE9_40") (pintype "passive"))
      (node (ref "U8") (pin "1") (pinfunction "1_1") (pintype "passive"))
    )
    (net (code "50") (name "/PWM_B") (class "Default")
      (node (ref "U8") (pin "6") (pinfunction "6_6") (pintype "passive"))
    )
    (net (code "51") (name "/PWM_BN") (class "Default")
      (node (ref "U7") (pin "6") (pinfunction "6_6") (pintype "passive"))
    )
    (net (code "52") (name "/PWM_BN_uC") (class "Default")
      (node (ref "U5") (pin "41") (pinfunction "PE10_41") (pintype "passive"))
      (node (ref "U7") (pin "4") (pinfunction "4_4") (pintype "passive"))
    )
    (net (code "53") (name "/PWM_B_uC") (class "Default")
      (node (ref "U5") (pin "42") (pinfunction "PE11_42") (pintype "passive"))
      (node (ref "U8") (pin "4") (pinfunction "4_4") (pintype "passive"))
    )
    (net (code "54") (name "/PWM_C") (class "Default")
      (node (ref "U8") (pin "8") (pinfunction "8_8") (pintype "passive"))
    )
    (net (code "55") (name "/PWM_CN") (class "Default")
      (node (ref "U7") (pin "8") (pinfunction "8_8") (pintype "passive"))
    )
    (net (code "56") (name "/PWM_CN_uC") (class "Default")
      (node (ref "U5") (pin "43") (pinfunction "PE12_43") (pintype "passive"))
      (node (ref "U7") (pin "9") (pinfunction "9_9") (pintype "passive"))
    )
    (net (code "57") (name "/PWM_C_uC") (class "Default")
      (node (ref "U5") (pin "44") (pinfunction "PE13_44") (pintype "passive"))
      (node (ref "U8") (pin "9") (pinfunction "9_9") (pintype "passive"))
    )
    (net (code "58") (name "/SCL") (class "Default")
      (node (ref "R41") (pin "2") (pinfunction "2_2") (pintype "passive"))
      (node (ref "U5") (pin "95") (pinfunction "PB8_95") (pintype "passive"))
      (node (ref "U6") (pin "6") (pinfunction "SCL_6") (pintype "passive"))
    )
    (net (code "59") (name "/SCOPE0") (class "Default")
      (node (ref "U5") (pin "53") (pinfunction "PB14_53") (pintype "passive"))
    )
    (net (code "60") (name "/SCOPE1") (class "Default")
      (node (ref "U5") (pin "54") (pinfunction "PB15_54") (pintype "passive"))
    )
    (net (code "61") (name "/SCOPE2") (class "Default")
      (node (ref "U5") (pin "55") (pinfunction "PD8_55") (pintype "passive"))
    )
    (net (code "62") (name "/SCOPE3") (class "Default")
      (node (ref "U5") (pin "56") (pinfunction "PD9_56") (pintype "passive"))
    )
    (net (code "63") (name "/SCOPE4") (class "Default")
      (node (ref "U5") (pin "57") (pinfunction "PD10_57") (pintype "passive"))
    )
    (net (code "64") (name "/SCOPE5") (class "Default")
      (node (ref "U5") (pin "58") (pinfunction "PD11_58") (pintype "passive"))
    )
    (net (code "65") (name "/SCOPE6") (class "Default")
      (node (ref "U5") (pin "59") (pinfunction "PD12_59") (pintype "passive"))
    )
    (net (code "66") (name "/SCOPE7") (class "Default")
      (node (ref "U5") (pin "60") (pinfunction "PD13_60") (pintype "passive"))
    )
    (net (code "67") (name "/SCOPE8") (class "Default")
      (node (ref "U5") (pin "61") (pinfunction "PD14_61") (pintype "passive"))
    )
    (net (code "68") (name "/SDA") (class "Default")
      (node (ref "R44") (pin "2") (pinfunction "2_2") (pintype "passive"))
      (node (ref "U5") (pin "96") (pinfunction "PB9_96") (pintype "passive"))
      (node (ref "U6") (pin "5") (pinfunction "SDA_5") (pintype "passive"))
    )
    (net (code "69") (name "/TEMP") (class "Default")
      (node (ref "R61") (pin "2") (pinfunction "2_2") (pintype "passive"))
    )
    (net (code "70") (name "/TEMPA1") (class "Default")
      (node (ref "U5") (pin "3") (pinfunction "PE4_3") (pintype "passive"))
    )
    (net (code "71") (name "/TEMPA2") (class "Default")
      (node (ref "U5") (pin "4") (pinfunction "PE5_4") (pintype "passive"))
    )
    (net (code "72") (name "/TEMPAN1") (class "Default")
      (node (ref "U5") (pin "1") (pinfunction "PE2_1") (pintype "passive"))
    )
    (net (code "73") (name "/TEMPAN2") (class "Default")
      (node (ref "U5") (pin "2") (pinfunction "PE3_2") (pintype "passive"))
    )
    (net (code "74") (name "/TEMPN") (class "Default")
      (node (ref "R70") (pin "2") (pinfunction "2_2") (pintype "passive"))
    )
    (net (code "75") (name "/TEMPN_ADC") (class "Default")
      (node (ref "C43") (pin "2") (pinfunction "2_2") (pintype "passive"))
      (node (ref "R70") (pin "1") (pinfunction "1_1") (pintype "passive"))
      (node (ref "R73") (pin "2") (pinfunction "2_2") (pintype "passive"))
      (node (ref "U5") (pin "30") (pinfunction "PA5_30") (pintype "passive"))
    )
    (net (code "76") (name "/TEMP_ADC") (class "Default")
      (node (ref "C37") (pin "2") (pinfunction "2_2") (pintype "passive"))
      (node (ref "R61") (pin "1") (pinfunction "1_1") (pintype "passive"))
      (node (ref "R64") (pin "2") (pinfunction "2_2") (pintype "passive"))
      (node (ref "U5") (pin "29") (pinfunction "PA4_29") (pintype "passive"))
    )
    (net (code "77") (name "/TERM_EN") (class "Default")
      (node (ref "U5") (pin "5") (pinfunction "PE6_5") (pintype "passive"))
    )
    (net (code "78") (name "/VA_ADC") (class "Default")
      (node (ref "C36") (pin "2") (pinfunction "2_2") (pintype "passive"))
      (node (ref "R60") (pin "1") (pinfunction "1_1") (pintype "passive"))
      (node (ref "R63") (pin "2") (pinfunction "2_2") (pintype "passive"))
      (node (ref "U5") (pin "15") (pinfunction "PC0_15") (pintype "passive"))
    )
    (net (code "79") (name "/VA_RAW") (class "Default")
      (node (ref "R60") (pin "2") (pinfunction "2_2") (pintype "passive"))
    )
    (net (code "80") (name "/VBUS_ADC") (class "Default")
      (node (ref "C48") (pin "2") (pinfunction "2_2") (pintype "passive"))
      (node (ref "R78") (pin "1") (pinfunction "1_1") (pintype "passive"))
      (node (ref "R81") (pin "2") (pinfunction "2_2") (pintype "passive"))
      (node (ref "U5") (pin "26") (pinfunction "PA3_26") (pintype "passive"))
    )
    (net (code "81") (name "/VBUS_RAW") (class "Default")
      (node (ref "R78") (pin "2") (pinfunction "2_2") (pintype "passive"))
    )
    (net (code "82") (name "/VB_ADC") (class "Default")
      (node (ref "C42") (pin "2") (pinfunction "2_2") (pintype "passive"))
      (node (ref "R69") (pin "1") (pinfunction "1_1") (pintype "passive"))
      (node (ref "R72") (pin "2") (pinfunction "2_2") (pintype "passive"))
      (node (ref "U5") (pin "16") (pinfunction "PC1_16") (pintype "passive"))
    )
    (net (code "83") (name "/VB_RAW") (class "Default")
      (node (ref "R69") (pin "2") (pinfunction "2_2") (pintype "passive"))
    )
    (net (code "84") (name "/VCAP_1") (class "Default")
      (node (ref "C21") (pin "1") (pinfunction "1_1") (pintype "passive"))
      (node (ref "U5") (pin "49") (pinfunction "VCAP_1_49") (pintype "passive"))
    )
    (net (code "85") (name "/VCAP_2") (class "Default")
      (node (ref "C20") (pin "1") (pinfunction "1_1") (pintype "passive"))
      (node (ref "U5") (pin "73") (pinfunction "VCAP_2_73") (pintype "passive"))
    )
    (net (code "86") (name "/VC_ADC") (class "Default")
      (node (ref "C47") (pin "2") (pinfunction "2_2") (pintype "passive"))
      (node (ref "R77") (pin "1") (pinfunction "1_1") (pintype "passive"))
      (node (ref "R80") (pin "2") (pinfunction "2_2") (pintype "passive"))
      (node (ref "U5") (pin "17") (pinfunction "PC2_17") (pintype "passive"))
    )
    (net (code "87") (name "/VC_RAW") (class "Default")
      (node (ref "R77") (pin "2") (pinfunction "2_2") (pintype "passive"))
    )
    (net (code "88") (name "/VGATE_ADC") (class "Default")
      (node (ref "C50") (pin "2") (pinfunction "2_2") (pintype "passive"))
      (node (ref "R84") (pin "1") (pinfunction "1_1") (pintype "passive"))
      (node (ref "R85") (pin "2") (pinfunction "2_2") (pintype "passive"))
      (node (ref "U5") (pin "33") (pinfunction "PC4_33") (pintype "passive"))
    )
    (net (code "89") (name "/VGATE_RAW") (class "Default")
      (node (ref "R84") (pin "2") (pinfunction "2_2") (pintype "passive"))
    )
    (net (code "90") (name "/VN_ADC") (class "Default")
      (node (ref "C49") (pin "2") (pinfunction "2_2") (pintype "passive"))
      (node (ref "R82") (pin "1") (pinfunction "1_1") (pintype "passive"))
      (node (ref "R83") (pin "2") (pinfunction "2_2") (pintype "passive"))
      (node (ref "U5") (pin "18") (pinfunction "PC3_18") (pintype "passive"))
    )
    (net (code "91") (name "/VN_RAW") (class "Default")
      (node (ref "R82") (pin "2") (pinfunction "2_2") (pintype "passive"))
    )
    (net (code "92") (name "/V_ERROR_LED") (class "Default")
      (node (ref "R47") (pin "1") (pinfunction "1_1") (pintype "passive"))
      (node (ref "U5") (pin "85") (pinfunction "PD4_85") (pintype "passive"))
    )
    (net (code "93") (name "/WARNING") (class "Default")
      (node (ref "R45") (pin "1") (pinfunction "1_1") (pintype "passive"))
      (node (ref "U5") (pin "87") (pinfunction "PD6_87") (pintype "passive"))
    )
    (net (code "94") (name "/~{HW_IERROR}") (class "Default")
      (node (ref "R50") (pin "2") (pinfunction "2_2") (pintype "passive"))
      (node (ref "U14") (pin "1") (pinfunction "OUT_1") (pintype "passive"))
      (node (ref "U14") (pin "14") (pinfunction "OUT_14") (pintype "passive"))
      (node (ref "U14") (pin "2") (pinfunction "OUT_2") (pintype "passive"))
      (node (ref "U5") (pin "46") (pinfunction "PE15_46") (pintype "passive"))
      (node (ref "U7") (pin "10") (pinfunction "10_10") (pintype "passive"))
      (node (ref "U7") (pin "2") (pinfunction "2_2") (pintype "passive"))
      (node (ref "U7") (pin "5") (pinfunction "5_5") (pintype "passive"))
      (node (ref "U8") (pin "10") (pinfunction "10_10") (pintype "passive"))
      (node (ref "U8") (pin "2") (pinfunction "2_2") (pintype "passive"))
      (node (ref "U8") (pin "5") (pinfunction "5_5") (pintype "passive"))
      (node (ref "U9") (pin "1") (pinfunction "OUT_1") (pintype "passive"))
      (node (ref "U9") (pin "14") (pinfunction "OUT_14") (pintype "passive"))
      (node (ref "U9") (pin "2") (pinfunction "OUT_2") (pintype "passive"))
    )
    (net (code "95") (name "GND") (class "Default")
      (node (ref "C10") (pin "2") (pinfunction "2_2") (pintype "passive"))
      (node (ref "C11") (pin "1") (pinfunction "1_1") (pintype "passive"))
      (node (ref "C12") (pin "1") (pinfunction "1_1") (pintype "passive"))
      (node (ref "C13") (pin "1") (pinfunction "1_1") (pintype "passive"))
      (node (ref "C14") (pin "1") (pinfunction "1_1") (pintype "passive"))
      (node (ref "C15") (pin "1") (pinfunction "1_1") (pintype "passive"))
      (node (ref "C16") (pin "1") (pinfunction "1_1") (pintype "passive"))
      (node (ref "C19") (pin "2") (pinfunction "2_2") (pintype "passive"))
      (node (ref "C20") (pin "2") (pinfunction "2_2") (pintype "passive"))
      (node (ref "C21") (pin "2") (pinfunction "2_2") (pintype "passive"))
      (node (ref "C22") (pin "2") (pinfunction "2_2") (pintype "passive"))
      (node (ref "C23") (pin "1") (pinfunction "1_1") (pintype "passive"))
      (node (ref "C24") (pin "1") (pinfunction "1_1") (pintype "passive"))
      (node (ref "C25") (pin "1") (pinfunction "1_1") (pintype "passive"))
      (node (ref "C27") (pin "2") (pinfunction "2_2") (pintype "passive"))
      (node (ref "C28") (pin "1") (pinfunction "1_1") (pintype "passive"))
      (node (ref "C29") (pin "1") (pinfunction "1_1") (pintype "passive"))
      (node (ref "C30") (pin "1") (pinfunction "1_1") (pintype "passive"))
      (node (ref "C33") (pin "2") (pinfunction "2_2") (pintype "passive"))
      (node (ref "C35") (pin "1") (pinfunction "1_1") (pintype "passive"))
      (node (ref "C36") (pin "1") (pinfunction "1_1") (pintype "passive"))
      (node (ref "C37") (pin "1") (pinfunction "1_1") (pintype "passive"))
      (node (ref "C38") (pin "2") (pinfunction "2_2") (pintype "passive"))
      (node (ref "C39") (pin "2") (pinfunction "2_2") (pintype "passive"))
      (node (ref "C40") (pin "1") (pinfunction "1_1") (pintype "passive"))
      (node (ref "C41") (pin "1") (pinfunction "1_1") (pintype "passive"))
      (node (ref "C42") (pin "1") (pinfunction "1_1") (pintype "passive"))
      (node (ref "C43") (pin "1") (pinfunction "1_1") (pintype "passive"))
      (node (ref "C44") (pin "1") (pinfunction "1_1") (pintype "passive"))
      (node (ref "C45") (pin "1") (pinfunction "1_1") (pintype "passive"))
      (node (ref "C46") (pin "1") (pinfunction "1_1") (pintype "passive"))
      (node (ref "C47") (pin "1") (pinfunction "1_1") (pintype "passive"))
      (node (ref "C48") (pin "1") (pinfunction "1_1") (pintype "passive"))
      (node (ref "C49") (pin "1") (pinfunction "1_1") (pintype "passive"))
      (node (ref "C50") (pin "1") (pinfunction "1_1") (pintype "passive"))
      (node (ref "C9") (pin "2") (pinfunction "2_2") (pintype "passive"))
      (node (ref "D17") (pin "3") (pinfunction "GND*_3") (pintype "passive"))
      (node (ref "D17") (pin "4") (pinfunction "GND_4") (pintype "passive"))
      (node (ref "D17") (pin "5") (pinfunction "GND*_5") (pintype "passive"))
      (node (ref "D17") (pin "8") (pinfunction "GND*_8") (pintype "passive"))
      (node (ref "D18") (pin "1") (pinfunction "Cathode_1") (pintype "passive"))
      (node (ref "D18") (pin "3") (pinfunction "Cathode_3") (pintype "passive"))
      (node (ref "D18") (pin "5") (pinfunction "Cathode_5") (pintype "passive"))
      (node (ref "D18") (pin "7") (pinfunction "Cathode_7") (pintype "passive"))
      (node (ref "D19") (pin "1") (pinfunction "Cathode_1") (pintype "passive"))
      (node (ref "D19") (pin "3") (pinfunction "Cathode_3") (pintype "passive"))
      (node (ref "D19") (pin "5") (pinfunction "Cathode_5") (pintype "passive"))
      (node (ref "D19") (pin "7") (pinfunction "Cathode_7") (pintype "passive"))
      (node (ref "R37") (pin "2") (pinfunction "2_2") (pintype "passive"))
      (node (ref "R42") (pin "2") (pinfunction "2_2") (pintype "passive"))
      (node (ref "R53") (pin "2") (pinfunction "2_2") (pintype "passive"))
      (node (ref "R56") (pin "2") (pinfunction "2_2") (pintype "passive"))
      (node (ref "R62") (pin "1") (pinfunction "1_1") (pintype "passive"))
      (node (ref "R63") (pin "1") (pinfunction "1_1") (pintype "passive"))
      (node (ref "R64") (pin "1") (pinfunction "1_1") (pintype "passive"))
      (node (ref "R66") (pin "2") (pinfunction "2_2") (pintype "passive"))
      (node (ref "R67") (pin "2") (pinfunction "2_2") (pintype "passive"))
      (node (ref "R71") (pin "1") (pinfunction "1_1") (pintype "passive"))
      (node (ref "R72") (pin "1") (pinfunction "1_1") (pintype "passive"))
      (node (ref "R73") (pin "1") (pinfunction "1_1") (pintype "passive"))
      (node (ref "R79") (pin "1") (pinfunction "1_1") (pintype "passive"))
      (node (ref "R80") (pin "1") (pinfunction "1_1") (pintype "passive"))
      (node (ref "R81") (pin "1") (pinfunction "1_1") (pintype "passive"))
      (node (ref "R83") (pin "1") (pinfunction "1_1") (pintype "passive"))
      (node (ref "R85") (pin "1") (pinfunction "1_1") (pintype "passive"))
      (node (ref "SW1") (pin "2") (pinfunction "2_2") (pintype "passive"))
      (node (ref "U12") (pin "13") (pinfunction "V-_13") (pintype "passive"))
      (node (ref "U14") (pin "12") (pinfunction "GND_12") (pintype "passive"))
      (node (ref "U5") (pin "10") (pinfunction "VSS_10") (pintype "passive"))
      (node (ref "U5") (pin "20") (pinfunction "VSSA_20") (pintype "passive"))
      (node (ref "U5") (pin "27") (pinfunction "VSS_27") (pintype "passive"))
      (node (ref "U5") (pin "74") (pinfunction "VSS_74") (pintype "passive"))
      (node (ref "U5") (pin "99") (pinfunction "VSS_99") (pintype "passive"))
      (node (ref "U6") (pin "4") (pinfunction "VSS_4") (pintype "passive"))
      (node (ref "U6") (pin "7") (pinfunction "WP_7") (pintype "passive"))
      (node (ref "U7") (pin "12") (pinfunction "12_12") (pintype "passive"))
      (node (ref "U7") (pin "13") (pinfunction "13_13") (pintype "passive"))
      (node (ref "U7") (pin "7") (pinfunction "V-_7") (pintype "passive"))
      (node (ref "U8") (pin "12") (pinfunction "12_12") (pintype "passive"))
      (node (ref "U8") (pin "13") (pinfunction "13_13") (pintype "passive"))
      (node (ref "U8") (pin "7") (pinfunction "V-_7") (pintype "passive"))
      (node (ref "U9") (pin "12") (pinfunction "GND_12") (pintype "passive"))
    )
    (net (code "96") (name "Net-(D18A-Anode)") (class "Default")
      (node (ref "D18") (pin "2") (pinfunction "Anode_2") (pintype "passive"))
      (node (ref "R40") (pin "2") (pinfunction "2_2") (pintype "passive"))
    )
    (net (code "97") (name "Net-(D18B-Anode)") (class "Default")
      (node (ref "D18") (pin "4") (pinfunction "Anode_4") (pintype "passive"))
      (node (ref "R39") (pin "2") (pinfunction "2_2") (pintype "passive"))
    )
    (net (code "98") (name "Net-(D18C-Anode)") (class "Default")
      (node (ref "D18") (pin "6") (pinfunction "Anode_6") (pintype "passive"))
      (node (ref "R45") (pin "2") (pinfunction "2_2") (pintype "passive"))
    )
    (net (code "99") (name "Net-(D18D-Anode)") (class "Default")
      (node (ref "D18") (pin "8") (pinfunction "Anode_8") (pintype "passive"))
      (node (ref "R34") (pin "2") (pinfunction "2_2") (pintype "passive"))
    )
    (net (code "100") (name "Net-(D19A-Anode)") (class "Default")
      (node (ref "D19") (pin "2") (pinfunction "Anode_2") (pintype "passive"))
      (node (ref "R46") (pin "2") (pinfunction "2_2") (pintype "passive"))
    )
    (net (code "101") (name "Net-(D19B-Anode)") (class "Default")
      (node (ref "D19") (pin "4") (pinfunction "Anode_4") (pintype "passive"))
      (node (ref "R47") (pin "2") (pinfunction "2_2") (pintype "passive"))
    )
    (net (code "102") (name "Net-(D19C-Anode)") (class "Default")
      (node (ref "D19") (pin "6") (pinfunction "Anode_6") (pintype "passive"))
      (node (ref "R48") (pin "2") (pinfunction "2_2") (pintype "passive"))
    )
    (net (code "103") (name "Net-(D19D-Anode)") (class "Default")
      (node (ref "D19") (pin "8") (pinfunction "Anode_8") (pintype "passive"))
      (node (ref "R49") (pin "2") (pinfunction "2_2") (pintype "passive"))
    )
    (net (code "104") (name "Net-(U5-VDDA)") (class "Default")
      (node (ref "C23") (pin "2") (pinfunction "2_2") (pintype "passive"))
      (node (ref "C24") (pin "2") (pinfunction "2_2") (pintype "passive"))
      (node (ref "L1") (pin "2") (pinfunction "2_2") (pintype "passive"))
      (node (ref "U5") (pin "22") (pinfunction "VDDA_22") (pintype "passive"))
    )
    (net (code "105") (name "Net-(U12A-+)") (class "Default")
      (node (ref "C39") (pin "1") (pinfunction "1_1") (pintype "passive"))
      (node (ref "R65") (pin "1") (pinfunction "1_1") (pintype "passive"))
      (node (ref "U12") (pin "3") (pinfunction "+_3") (pintype "passive"))
    )
    (net (code "106") (name "Net-(U12B-+)") (class "Default")
      (node (ref "R58") (pin "2") (pinfunction "2_2") (pintype "passive"))
      (node (ref "R66") (pin "1") (pinfunction "1_1") (pintype "passive"))
      (node (ref "U12") (pin "12") (pinfunction "+_12") (pintype "passive"))
      (node (ref "U12") (pin "14") (pinfunction "+_14") (pintype "passive"))
      (node (ref "U12") (pin "5") (pinfunction "+_5") (pintype "passive"))
    )
    (net (code "107") (name "Net-(U12B--)") (class "Default")
      (node (ref "U12") (pin "6") (pinfunction "-_6") (pintype "passive"))
      (node (ref "U12") (pin "7") (pinfunction "7_7") (pintype "passive"))
    )
    (net (code "108") (name "Net-(U12C--)") (class "Default")
      (node (ref "U12") (pin "10") (pinfunction "10_10") (pintype "passive"))
      (node (ref "U12") (pin "11") (pinfunction "-_11") (pintype "passive"))
    )
    (net (code "109") (name "Net-(U12D--)") (class "Default")
      (node (ref "U12") (pin "15") (pinfunction "-_15") (pintype "passive"))
      (node (ref "U12") (pin "16") (pinfunction "16_16") (pintype "passive"))
    )
    (net (code "110") (name "unconnected-(U5-PA7-Pad32)") (class "Default")
      (node (ref "U5") (pin "32") (pinfunction "PA7_32") (pintype "passive"))
    )
    (net (code "111") (name "unconnected-(U5-PA9-Pad68)") (class "Default")
      (node (ref "U5") (pin "68") (pinfunction "PA9_68") (pintype "passive"))
    )
    (net (code "112") (name "unconnected-(U5-PA10-Pad69)") (class "Default")
      (node (ref "U5") (pin "69") (pinfunction "PA10_69") (pintype "passive"))
    )
    (net (code "113") (name "unconnected-(U5-PA11-Pad70)") (class "Default")
      (node (ref "U5") (pin "70") (pinfunction "PA11_70") (pintype "passive"))
    )
    (net (code "114") (name "unconnected-(U5-PA12-Pad71)") (class "Default")
      (node (ref "U5") (pin "71") (pinfunction "PA12_71") (pintype "passive"))
    )
    (net (code "115") (name "unconnected-(U5-PB6-Pad92)") (class "Default")
      (node (ref "U5") (pin "92") (pinfunction "PB6_92") (pintype "passive"))
    )
    (net (code "116") (name "unconnected-(U5-PB7-Pad93)") (class "Default")
      (node (ref "U5") (pin "93") (pinfunction "PB7_93") (pintype "passive"))
    )
    (net (code "117") (name "unconnected-(U5-PC10-Pad78)") (class "Default")
      (node (ref "U5") (pin "78") (pinfunction "PC10_78") (pintype "passive"))
    )
    (net (code "118") (name "unconnected-(U5-PC11-Pad79)") (class "Default")
      (node (ref "U5") (pin "79") (pinfunction "PC11_79") (pintype "passive"))
    )
    (net (code "119") (name "unconnected-(U5-PC12-Pad80)") (class "Default")
      (node (ref "U5") (pin "80") (pinfunction "PC12_80") (pintype "passive"))
    )
    (net (code "120") (name "unconnected-(U5-PC13-Pad7)") (class "Default")
      (node (ref "U5") (pin "7") (pinfunction "PC13_7") (pintype "passive"))
    )
    (net (code "121") (name "unconnected-(U5-PC14-Pad8)") (class "Default")
      (node (ref "U5") (pin "8") (pinfunction "PC14_8") (pintype "passive"))
    )
    (net (code "122") (name "unconnected-(U5-PC15-Pad9)") (class "Default")
      (node (ref "U5") (pin "9") (pinfunction "PC15_9") (pintype "passive"))
    )
    (net (code "123") (name "unconnected-(U5-PE1-Pad98)") (class "Default")
      (node (ref "U5") (pin "98") (pinfunction "PE1_98") (pintype "passive"))
    )
    (net (code "124") (name "unconnected-(U5-PE7-Pad38)") (class "Default")
      (node (ref "U5") (pin "38") (pinfunction "PE7_38") (pintype "passive"))
    )
    (net (code "125") (name "unconnected-(U5-PE14-Pad45)") (class "Default")
      (node (ref "U5") (pin "45") (pinfunction "PE14_45") (pintype "passive"))
    )
    (net (code "126") (name "unconnected-(U6-NC-Pad1)") (class "Default")
      (node (ref "U6") (pin "1") (pinfunction "NC_1") (pintype "passive"))
    )
    (net (code "127") (name "unconnected-(U6-NC-Pad2)") (class "Default")
      (node (ref "U6") (pin "2") (pinfunction "NC_2") (pintype "passive"))
    )
    (net (code "128") (name "unconnected-(U6-NC-Pad3)") (class "Default")
      (node (ref "U6") (pin "3") (pinfunction "NC_3") (pintype "passive"))
    )
    (net (code "129") (name "unconnected-(U7-Pad11)") (class "Default")
      (node (ref "U7") (pin "11") (pinfunction "11_11") (pintype "passive"))
    )
    (net (code "130") (name "unconnected-(U8-Pad11)") (class "Default")
      (node (ref "U8") (pin "11") (pinfunction "11_11") (pintype "passive"))
    )
    (net (code "131") (name "unconnected-(U9D-OUT-Pad13)") (class "Default")
      (node (ref "U9") (pin "13") (pinfunction "OUT_13") (pintype "passive"))
    )
    (net (code "132") (name "unconnected-(U14D-OUT-Pad13)") (class "Default")
      (node (ref "U14") (pin "13") (pinfunction "OUT_13") (pintype "passive"))
    )
  )
)
